# 4WireTouch.net
KiCad netlist of a schematic drawn in EAGLE
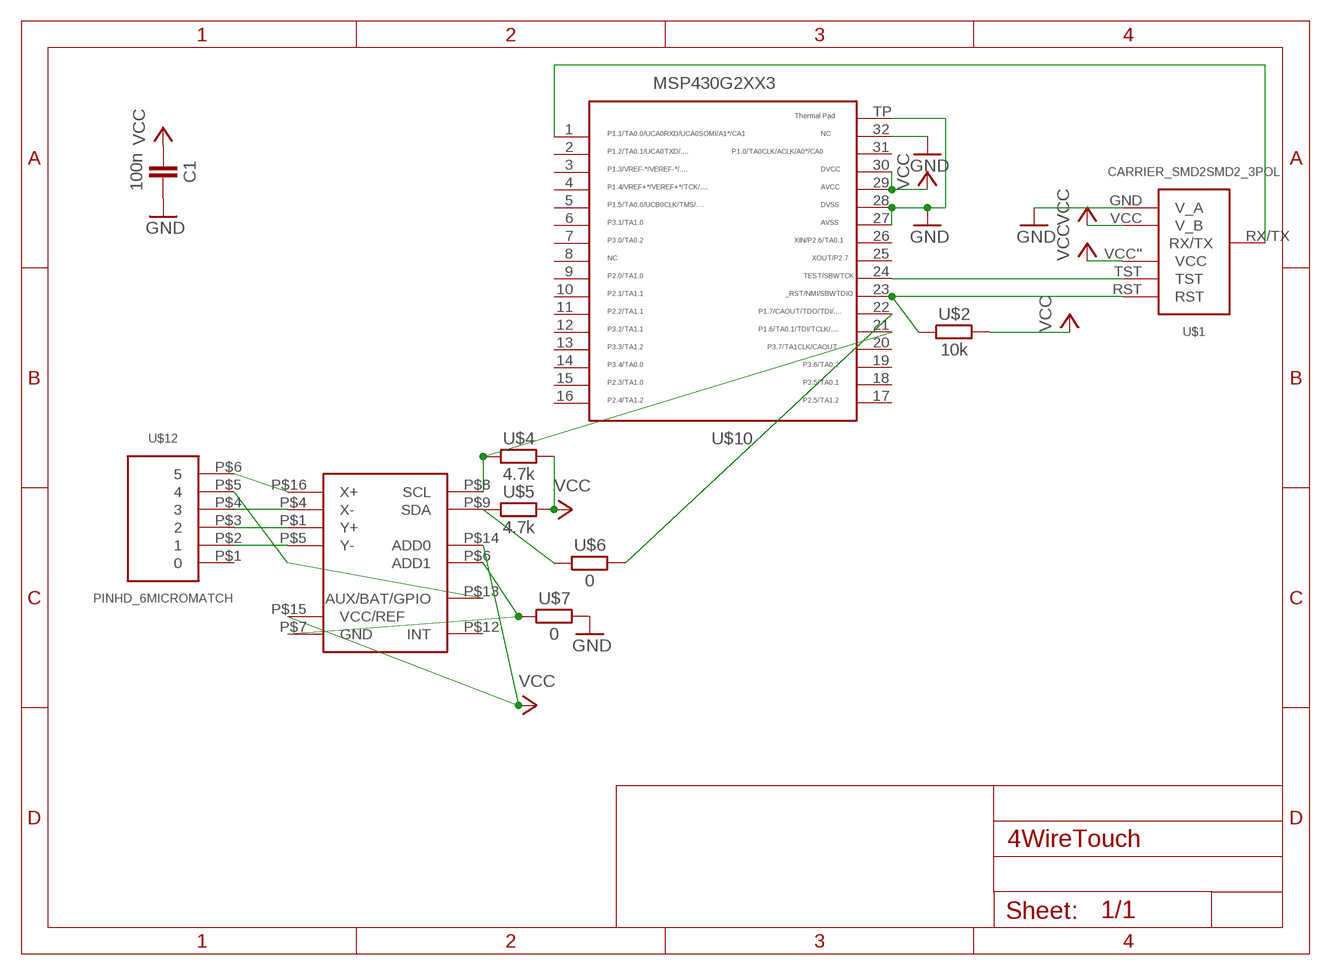
[diagram p0: schematic, sheet 1]

(export (version "E")
  (design (tool "Eeschema 10.0.6"))
  (components
    (comp (ref "C1")
      (value "100n")
      (footprint "eagle-import:603")
      (libsource (lib "eagle-import") (part "CAPACITOR"))
    )
    (comp (ref "U$1")
      (value "CARRIER_SMD2SMD2_3POL")
      (footprint "eagle-import:CARRIER_SMD2_3POL")
      (libsource (lib "eagle-import") (part "CARRIER_SMD2SMD2_3POL"))
    )
    (comp (ref "U$2")
      (value "10k")
      (footprint "eagle-import:603")
      (libsource (lib "eagle-import") (part "RESISTOR0603"))
    )
    (comp (ref "U$3")
      (value "AD7879")
      (footprint "eagle-import:LFCSP")
      (libsource (lib "eagle-import") (part "AD7879"))
    )
    (comp (ref "U$4")
      (value "4.7k")
      (footprint "eagle-import:603")
      (libsource (lib "eagle-import") (part "RESISTOR0603"))
    )
    (comp (ref "U$5")
      (value "4.7k")
      (footprint "eagle-import:603")
      (libsource (lib "eagle-import") (part "RESISTOR0603"))
    )
    (comp (ref "U$6")
      (value "0")
      (footprint "eagle-import:603")
      (libsource (lib "eagle-import") (part "RESISTOR0603"))
    )
    (comp (ref "U$7")
      (value "0")
      (footprint "eagle-import:603")
      (libsource (lib "eagle-import") (part "RESISTOR0603"))
    )
    (comp (ref "U$10")
      (value "MSP430G2553")
      (footprint "eagle-import:QFN32")
      (libsource (lib "eagle-import") (part "MSP430G2553"))
    )
    (comp (ref "U$12")
      (value "PINHD_6MICROMATCH")
      (footprint "eagle-import:MICROMATCH6POL")
      (libsource (lib "eagle-import") (part "PINHD_6MICROMATCH"))
    )
  )
  (nets
    (net (code "1") (name "GND") (class "Default")
      (node (ref "C1") (pin "2") (pinfunction "2_2") (pintype "passive"))
      (node (ref "U$1") (pin "GND") (pinfunction "V_A_GND") (pintype "bidirectional"))
      (node (ref "U$10") (pin "27") (pinfunction "27_27") (pintype "bidirectional"))
      (node (ref "U$10") (pin "28") (pinfunction "28_28") (pintype "bidirectional"))
      (node (ref "U$10") (pin "32") (pinfunction "32_32") (pintype "bidirectional"))
      (node (ref "U$10") (pin "TP") (pinfunction "TP_TP") (pintype "bidirectional"))
      (node (ref "U$7") (pin "2") (pinfunction "2_2") (pintype "passive"))
    )
    (net (code "2") (name "Net-(U$1-PadRST)") (class "Default")
      (node (ref "U$1") (pin "RST") (pinfunction "RST_RST") (pintype "bidirectional"))
      (node (ref "U$10") (pin "23") (pinfunction "23_23") (pintype "bidirectional"))
      (node (ref "U$2") (pin "1") (pinfunction "1_1") (pintype "passive"))
    )
    (net (code "3") (name "Net-(U$1-PadRX{slash}TX)") (class "Default")
      (node (ref "U$1") (pin "RX/TX") (pinfunction "RX/TX_RX/TX") (pintype "bidirectional"))
      (node (ref "U$10") (pin "1") (pinfunction "1_1") (pintype "bidirectional"))
    )
    (net (code "4") (name "Net-(U$1-PadTST)") (class "Default")
      (node (ref "U$1") (pin "TST") (pinfunction "TST_TST") (pintype "bidirectional"))
      (node (ref "U$10") (pin "24") (pinfunction "24_24") (pintype "bidirectional"))
    )
    (net (code "5") (name "Net-(U$3-ADD1)") (class "Default")
      (node (ref "U$3") (pin "P$6") (pinfunction "ADD1_P$6") (pintype "bidirectional"))
      (node (ref "U$3") (pin "P$7") (pinfunction "GND_P$7") (pintype "bidirectional"))
      (node (ref "U$7") (pin "1") (pinfunction "1_1") (pintype "passive"))
    )
    (net (code "6") (name "Net-(U$3-SCL)") (class "Default")
      (node (ref "U$10") (pin "21") (pinfunction "21_21") (pintype "bidirectional"))
      (node (ref "U$3") (pin "P$8") (pinfunction "SCL_P$8") (pintype "bidirectional"))
      (node (ref "U$4") (pin "1") (pinfunction "1_1") (pintype "passive"))
    )
    (net (code "7") (name "Net-(U$3-SDA)") (class "Default")
      (node (ref "U$3") (pin "P$9") (pinfunction "SDA_P$9") (pintype "bidirectional"))
      (node (ref "U$5") (pin "1") (pinfunction "1_1") (pintype "passive"))
      (node (ref "U$6") (pin "1") (pinfunction "1_1") (pintype "passive"))
    )
    (net (code "8") (name "Net-(U$10-Pad22)") (class "Default")
      (node (ref "U$10") (pin "22") (pinfunction "22_22") (pintype "bidirectional"))
      (node (ref "U$6") (pin "2") (pinfunction "2_2") (pintype "passive"))
    )
    (net (code "9") (name "Net-(U$12-1)") (class "Default")
      (node (ref "U$12") (pin "P$2") (pinfunction "1_P$2") (pintype "bidirectional"))
      (node (ref "U$3") (pin "P$5") (pinfunction "Y-_P$5") (pintype "bidirectional"))
    )
    (net (code "10") (name "Net-(U$12-2)") (class "Default")
      (node (ref "U$12") (pin "P$3") (pinfunction "2_P$3") (pintype "bidirectional"))
      (node (ref "U$3") (pin "P$1") (pinfunction "Y+_P$1") (pintype "bidirectional"))
    )
    (net (code "11") (name "Net-(U$12-3)") (class "Default")
      (node (ref "U$12") (pin "P$4") (pinfunction "3_P$4") (pintype "bidirectional"))
      (node (ref "U$3") (pin "P$4") (pinfunction "X-_P$4") (pintype "bidirectional"))
    )
    (net (code "12") (name "Net-(U$12-4)") (class "Default")
      (node (ref "U$12") (pin "P$5") (pinfunction "4_P$5") (pintype "bidirectional"))
      (node (ref "U$3") (pin "P$13") (pinfunction "AUX/BAT/GPIO_P$13") (pintype "bidirectional"))
    )
    (net (code "13") (name "Net-(U$12-5)") (class "Default")
      (node (ref "U$12") (pin "P$6") (pinfunction "5_P$6") (pintype "bidirectional"))
      (node (ref "U$3") (pin "P$16") (pinfunction "X+_P$16") (pintype "bidirectional"))
    )
    (net (code "14") (name "VCC") (class "Default")
      (node (ref "C1") (pin "1") (pinfunction "1_1") (pintype "passive"))
      (node (ref "U$1") (pin "VCC") (pinfunction "V_B_VCC") (pintype "bidirectional"))
      (node (ref "U$1") (pin "VCC''") (pinfunction "VCC_VCC''") (pintype "bidirectional"))
      (node (ref "U$10") (pin "29") (pinfunction "29_29") (pintype "bidirectional"))
      (node (ref "U$10") (pin "30") (pinfunction "30_30") (pintype "bidirectional"))
      (node (ref "U$2") (pin "2") (pinfunction "2_2") (pintype "passive"))
      (node (ref "U$3") (pin "P$14") (pinfunction "ADD0_P$14") (pintype "bidirectional"))
      (node (ref "U$3") (pin "P$15") (pinfunction "VCC/REF_P$15") (pintype "bidirectional"))
      (node (ref "U$4") (pin "2") (pinfunction "2_2") (pintype "passive"))
      (node (ref "U$5") (pin "2") (pinfunction "2_2") (pintype "passive"))
    )
    (net (code "15") (name "unconnected-(U$3-INT-PadP$12)") (class "Default")
      (node (ref "U$3") (pin "P$12") (pinfunction "INT_P$12") (pintype "bidirectional"))
    )
    (net (code "16") (name "unconnected-(U$10-Pad2)") (class "Default")
      (node (ref "U$10") (pin "2") (pinfunction "2_2") (pintype "bidirectional"))
    )
    (net (code "17") (name "unconnected-(U$10-Pad3)") (class "Default")
      (node (ref "U$10") (pin "3") (pinfunction "3_3") (pintype "bidirectional"))
    )
    (net (code "18") (name "unconnected-(U$10-Pad4)") (class "Default")
      (node (ref "U$10") (pin "4") (pinfunction "4_4") (pintype "bidirectional"))
    )
    (net (code "19") (name "unconnected-(U$10-Pad5)") (class "Default")
      (node (ref "U$10") (pin "5") (pinfunction "5_5") (pintype "bidirectional"))
    )
    (net (code "20") (name "unconnected-(U$10-Pad6)") (class "Default")
      (node (ref "U$10") (pin "6") (pinfunction "6_6") (pintype "bidirectional"))
    )
    (net (code "21") (name "unconnected-(U$10-Pad7)") (class "Default")
      (node (ref "U$10") (pin "7") (pinfunction "7_7") (pintype "bidirectional"))
    )
    (net (code "22") (name "unconnected-(U$10-Pad8)") (class "Default")
      (node (ref "U$10") (pin "8") (pinfunction "8_8") (pintype "bidirectional"))
    )
    (net (code "23") (name "unconnected-(U$10-Pad9)") (class "Default")
      (node (ref "U$10") (pin "9") (pinfunction "9_9") (pintype "bidirectional"))
    )
    (net (code "24") (name "unconnected-(U$10-Pad10)") (class "Default")
      (node (ref "U$10") (pin "10") (pinfunction "10_10") (pintype "bidirectional"))
    )
    (net (code "25") (name "unconnected-(U$10-Pad11)") (class "Default")
      (node (ref "U$10") (pin "11") (pinfunction "11_11") (pintype "bidirectional"))
    )
    (net (code "26") (name "unconnected-(U$10-Pad12)") (class "Default")
      (node (ref "U$10") (pin "12") (pinfunction "12_12") (pintype "bidirectional"))
    )
    (net (code "27") (name "unconnected-(U$10-Pad13)") (class "Default")
      (node (ref "U$10") (pin "13") (pinfunction "13_13") (pintype "bidirectional"))
    )
    (net (code "28") (name "unconnected-(U$10-Pad14)") (class "Default")
      (node (ref "U$10") (pin "14") (pinfunction "14_14") (pintype "bidirectional"))
    )
    (net (code "29") (name "unconnected-(U$10-Pad15)") (class "Default")
      (node (ref "U$10") (pin "15") (pinfunction "15_15") (pintype "bidirectional"))
    )
    (net (code "30") (name "unconnected-(U$10-Pad16)") (class "Default")
      (node (ref "U$10") (pin "16") (pinfunction "16_16") (pintype "bidirectional"))
    )
    (net (code "31") (name "unconnected-(U$10-Pad17)") (class "Default")
      (node (ref "U$10") (pin "17") (pinfunction "17_17") (pintype "bidirectional"))
    )
    (net (code "32") (name "unconnected-(U$10-Pad18)") (class "Default")
      (node (ref "U$10") (pin "18") (pinfunction "18_18") (pintype "bidirectional"))
    )
    (net (code "33") (name "unconnected-(U$10-Pad19)") (class "Default")
      (node (ref "U$10") (pin "19") (pinfunction "19_19") (pintype "bidirectional"))
    )
    (net (code "34") (name "unconnected-(U$10-Pad20)") (class "Default")
      (node (ref "U$10") (pin "20") (pinfunction "20_20") (pintype "bidirectional"))
    )
    (net (code "35") (name "unconnected-(U$10-Pad25)") (class "Default")
      (node (ref "U$10") (pin "25") (pinfunction "25_25") (pintype "bidirectional"))
    )
    (net (code "36") (name "unconnected-(U$10-Pad26)") (class "Default")
      (node (ref "U$10") (pin "26") (pinfunction "26_26") (pintype "bidirectional"))
    )
    (net (code "37") (name "unconnected-(U$10-Pad31)") (class "Default")
      (node (ref "U$10") (pin "31") (pinfunction "31_31") (pintype "bidirectional"))
    )
    (net (code "38") (name "unconnected-(U$12-0-PadP$1)") (class "Default")
      (node (ref "U$12") (pin "P$1") (pinfunction "0_P$1") (pintype "bidirectional"))
    )
  )
)
